# Accel.net
KiCad netlist of a schematic drawn in Altium Designer
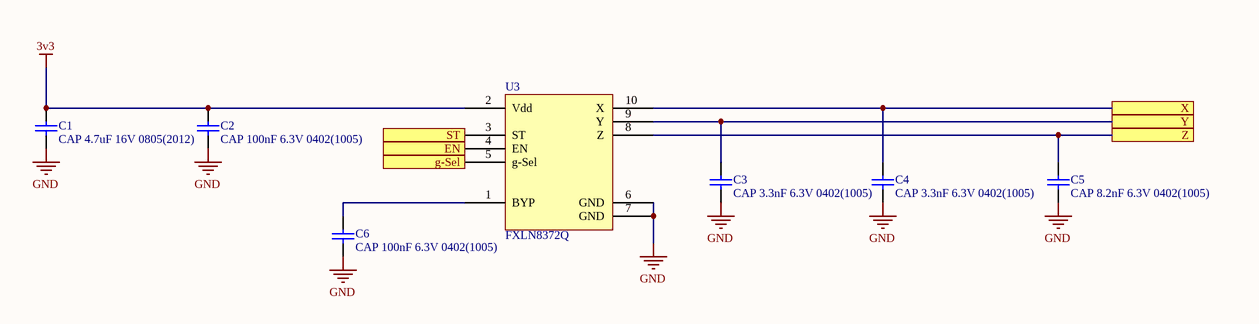
[diagram p0: Accel.SchDoc]

(export (version "E")
  (design (tool "Eeschema 10.0.6"))
  (components
    (comp (ref "C1")
      (value "CAP 4.7uF 16V 0805(2012)")
      (footprint "CAPC0805(2012)155_M")
      (description "CAP 4.7uF 16V ±20% 0805 (2012 Metric) Thickness 1.55mm SMD")
      (fields (field (name "TOLERANCE") "Â±20%"))
      (libsource (lib "Altium Content Vault") (part "CAP"))
    )
    (comp (ref "C2")
      (value "CAP 100nF 6.3V 0402(1005)")
      (footprint "CAPC0402(1005)60_M")
      (description "CAP 100nF 6.3V ±20% 0402 (1005 Metric) Thickness 0.6mm SMD")
      (fields (field (name "TOLERANCE") "Â±20%"))
      (libsource (lib "Altium Content Vault") (part "CAP"))
    )
    (comp (ref "C3")
      (value "CAP 3.3nF 6.3V 0402(1005)")
      (footprint "CAPC0402(1005)60_M")
      (description "CAP 3.3nF 6.3V ±20% 0402 (1005 Metric) Thickness 0.6mm SMD")
      (fields (field (name "TOLERANCE") "Â±20%"))
      (libsource (lib "Altium Content Vault") (part "CAP"))
    )
    (comp (ref "C4")
      (value "CAP 3.3nF 6.3V 0402(1005)")
      (footprint "CAPC0402(1005)60_M")
      (description "CAP 3.3nF 6.3V ±20% 0402 (1005 Metric) Thickness 0.6mm SMD")
      (fields (field (name "TOLERANCE") "Â±20%"))
      (libsource (lib "Altium Content Vault") (part "CAP"))
    )
    (comp (ref "C5")
      (value "CAP 8.2nF 6.3V 0402(1005)")
      (footprint "CAPC0402(1005)60_L")
      (description "CAP 8.2nF 6.3V ±20% 0402 (1005 Metric) Thickness 0.6mm SMD")
      (fields (field (name "TOLERANCE") "Â±20%"))
      (libsource (lib "Altium Content Vault") (part "CAP"))
    )
    (comp (ref "C6")
      (value "CAP 100nF 6.3V 0402(1005)")
      (footprint "CAPC0402(1005)60_M")
      (description "CAP 100nF 6.3V ±20% 0402 (1005 Metric) Thickness 0.6mm SMD")
      (fields (field (name "TOLERANCE") "Â±20%"))
      (libsource (lib "Altium Content Vault") (part "CAP"))
    )
    (comp (ref "U3")
      (value "FXLN8372Q")
      (footprint "QFN65P300X300X100-12N")
      (description "Xtrinsic FXLN83xxQ 3-Axis Low-Power Analog-Output Accelerometer")
      (libsource (lib "parts") (part "FXLN8372Q"))
    )
  )
  (nets
    (net (code "1") (name "/EN") (class "Default")
      (node (ref "U3") (pin "4") (pinfunction "EN_4") (pintype "passive"))
    )
    (net (code "2") (name "/ST") (class "Default")
      (node (ref "U3") (pin "3") (pinfunction "ST_3") (pintype "passive"))
    )
    (net (code "3") (name "/X") (class "Default")
      (node (ref "C4") (pin "2") (pinfunction "2_2") (pintype "passive"))
      (node (ref "U3") (pin "10") (pinfunction "X_10") (pintype "passive"))
    )
    (net (code "4") (name "/Y") (class "Default")
      (node (ref "C3") (pin "2") (pinfunction "2_2") (pintype "passive"))
      (node (ref "U3") (pin "9") (pinfunction "Y_9") (pintype "passive"))
    )
    (net (code "5") (name "/Z") (class "Default")
      (node (ref "C5") (pin "2") (pinfunction "2_2") (pintype "passive"))
      (node (ref "U3") (pin "8") (pinfunction "Z_8") (pintype "passive"))
    )
    (net (code "6") (name "/g-Sel") (class "Default")
      (node (ref "U3") (pin "5") (pinfunction "g-Sel_5") (pintype "passive"))
    )
    (net (code "7") (name "3v3") (class "Default")
      (node (ref "C1") (pin "2") (pinfunction "2_2") (pintype "passive"))
      (node (ref "C2") (pin "2") (pinfunction "2_2") (pintype "passive"))
      (node (ref "U3") (pin "2") (pinfunction "Vdd_2") (pintype "passive"))
    )
    (net (code "8") (name "GND") (class "Default")
      (node (ref "C1") (pin "1") (pinfunction "1_1") (pintype "passive"))
      (node (ref "C2") (pin "1") (pinfunction "1_1") (pintype "passive"))
      (node (ref "C3") (pin "1") (pinfunction "1_1") (pintype "passive"))
      (node (ref "C4") (pin "1") (pinfunction "1_1") (pintype "passive"))
      (node (ref "C5") (pin "1") (pinfunction "1_1") (pintype "passive"))
      (node (ref "C6") (pin "1") (pinfunction "1_1") (pintype "passive"))
      (node (ref "U3") (pin "6") (pinfunction "GND_6") (pintype "passive"))
      (node (ref "U3") (pin "7") (pinfunction "GND_7") (pintype "passive"))
    )
    (net (code "9") (name "Net-(U3-BYP)") (class "Default")
      (node (ref "C6") (pin "2") (pinfunction "2_2") (pintype "passive"))
      (node (ref "U3") (pin "1") (pinfunction "BYP_1") (pintype "passive"))
    )
  )
)
